# LowTemp_board_1.net
KiCad netlist of a schematic drawn in EAGLE
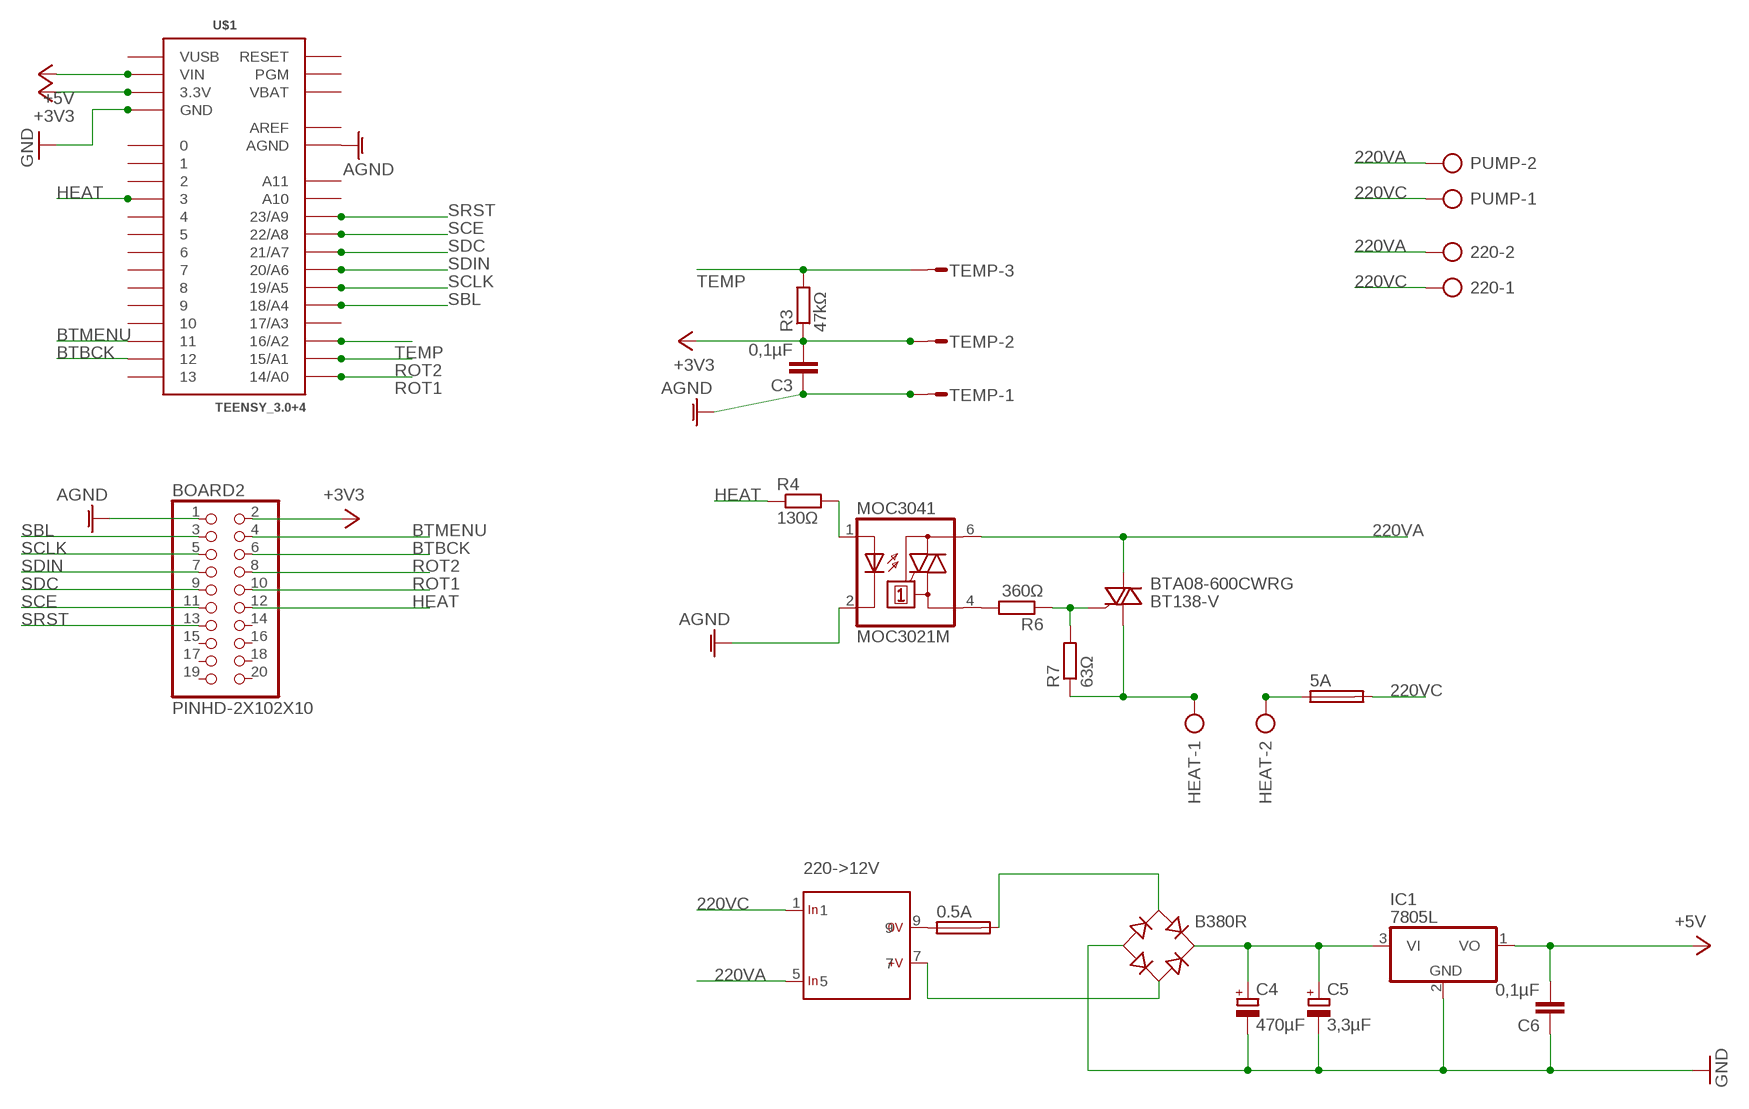
[diagram p0: schematic, sheet 1]

(export (version "E")
  (design (tool "Eeschema 10.0.6"))
  (components
    (comp (ref "0.5A")
      (value "SH22,5A")
      (footprint "eagle-import:SH22,5A")
      (fields (field (name "MPN") "0031.7701.11"))
      (libsource (lib "eagle-import") (part "SH22,5A"))
    )
    (comp (ref "5A")
      (value "SH22,5A")
      (footprint "eagle-import:SH22,5A")
      (fields (field (name "MPN") "0031.7701.11"))
      (libsource (lib "eagle-import") (part "SH22,5A"))
    )
    (comp (ref "220")
      (value "AK500/2-H")
      (footprint "eagle-import:AK500_2-H")
      (libsource (lib "eagle-import") (part "AK500/2-H"))
    )
    (comp (ref "220->12V")
      (value "SINGLE")
      (footprint "eagle-import:1")
      (libsource (lib "eagle-import") (part "SINGLE"))
    )
    (comp (ref "B380R")
      (value "RB1A")
      (footprint "eagle-import:RB1A")
      (libsource (lib "eagle-import") (part "RB1A"))
    )
    (comp (ref "BOARD2")
      (value "PINHD-2X102X10")
      (footprint "eagle-import:2X10")
      (libsource (lib "eagle-import") (part "PINHD-2X102X10"))
    )
    (comp (ref "BTA08-600CWRG")
      (value "BT138-V")
      (footprint "eagle-import:TO220BV")
      (libsource (lib "eagle-import") (part "BT138-V"))
    )
    (comp (ref "C3")
      (value "0,1µF")
      (footprint "eagle-import:C050-025X075")
      (libsource (lib "eagle-import") (part "C-EU050-025X075"))
    )
    (comp (ref "C4")
      (value "470µF")
      (footprint "eagle-import:E5-8,5")
      (libsource (lib "eagle-import") (part "CPOL-EUE5-8.5"))
    )
    (comp (ref "C5")
      (value "3,3µF")
      (footprint "eagle-import:TT2D4")
      (libsource (lib "eagle-import") (part "CPOL-EUTT2D4"))
    )
    (comp (ref "C6")
      (value "0,1µF")
      (footprint "eagle-import:C050-025X075")
      (libsource (lib "eagle-import") (part "C-EU050-025X075"))
    )
    (comp (ref "HEAT")
      (value "AK500/2-H")
      (footprint "eagle-import:AK500_2-H")
      (libsource (lib "eagle-import") (part "AK500/2-H"))
    )
    (comp (ref "IC1")
      (value "7805L")
      (footprint "eagle-import:TO92")
      (libsource (lib "eagle-import") (part "78L05"))
    )
    (comp (ref "MOC3041")
      (value "MOC3021M")
      (footprint "eagle-import:DIL06")
      (fields (field (name "MF") "FAIRCHILD SEMICONDUCTOR") (field (name "MPN") "MOC3021-M"))
      (libsource (lib "eagle-import") (part "MOC30M21"))
    )
    (comp (ref "PUMP")
      (value "AK500/2-H")
      (footprint "eagle-import:AK500_2-H")
      (libsource (lib "eagle-import") (part "AK500/2-H"))
    )
    (comp (ref "R3")
      (value "47kΩ")
      (footprint "eagle-import:0207_7")
      (libsource (lib "eagle-import") (part "R-EU_0207/7"))
    )
    (comp (ref "R4")
      (value "130Ω")
      (footprint "eagle-import:0207_7")
      (libsource (lib "eagle-import") (part "R-EU_0207/7"))
    )
    (comp (ref "R6")
      (value "360Ω")
      (footprint "eagle-import:0207_7")
      (libsource (lib "eagle-import") (part "R-EU_0207/7"))
    )
    (comp (ref "R7")
      (value "63Ω")
      (footprint "eagle-import:0207_7")
      (libsource (lib "eagle-import") (part "R-EU_0207/7"))
    )
    (comp (ref "TEMP")
      (value "S03P")
      (footprint "eagle-import:S03P")
      (libsource (lib "eagle-import") (part "S03P"))
    )
    (comp (ref "U$1")
      (value "TEENSY_3.0+4")
      (footprint "eagle-import:TEENSY_3.0+4")
      (libsource (lib "eagle-import") (part "TEENSY_3.0+4"))
    )
  )
  (nets
    (net (code "1") (name "+3V3") (class "Default")
      (node (ref "BOARD2") (pin "2") (pinfunction "2_2") (pintype "passive"))
      (node (ref "C3") (pin "2") (pinfunction "2_2") (pintype "passive"))
      (node (ref "R3") (pin "1") (pinfunction "1_1") (pintype "passive"))
      (node (ref "TEMP") (pin "2") (pinfunction "S_2") (pintype "passive"))
      (node (ref "U$1") (pin "3.3V") (pinfunction "3.3V_3.3V") (pintype "power_in"))
      (node (ref "U$1") (pin "3.3V1") (pinfunction "3.3V_3.3V1") (pintype "power_in"))
    )
    (net (code "2") (name "+5V") (class "Default")
      (node (ref "C6") (pin "2") (pinfunction "2_2") (pintype "passive"))
      (node (ref "IC1") (pin "1") (pinfunction "VO_1") (pintype "passive"))
      (node (ref "U$1") (pin "VIN") (pinfunction "VIN_VIN") (pintype "power_in"))
    )
    (net (code "3") (name "/220VA") (class "Default")
      (node (ref "220") (pin "2") (pinfunction "KL_2") (pintype "passive"))
      (node (ref "220->12V") (pin "5") (pinfunction "5_5") (pintype "input"))
      (node (ref "BTA08-600CWRG") (pin "T2") (pinfunction "A2_T2") (pintype "passive"))
      (node (ref "MOC3041") (pin "6") (pinfunction "A2_6") (pintype "passive"))
      (node (ref "PUMP") (pin "2") (pinfunction "KL_2") (pintype "passive"))
    )
    (net (code "4") (name "/220VC") (class "Default")
      (node (ref "220") (pin "1") (pinfunction "KL_1") (pintype "passive"))
      (node (ref "220->12V") (pin "1") (pinfunction "1_1") (pintype "input"))
      (node (ref "5A") (pin "2") (pinfunction "2_2") (pintype "passive"))
      (node (ref "PUMP") (pin "1") (pinfunction "KL_1") (pintype "passive"))
    )
    (net (code "5") (name "/AREF") (class "Default")
      (node (ref "U$1") (pin "AREF") (pinfunction "AREF_AREF") (pintype "power_in"))
    )
    (net (code "6") (name "/BTBCK") (class "Default")
      (node (ref "BOARD2") (pin "6") (pinfunction "6_6") (pintype "passive"))
      (node (ref "U$1") (pin "12") (pinfunction "12_12") (pintype "bidirectional"))
    )
    (net (code "7") (name "/BTMENU") (class "Default")
      (node (ref "BOARD2") (pin "4") (pinfunction "4_4") (pintype "passive"))
      (node (ref "U$1") (pin "11") (pinfunction "11_11") (pintype "bidirectional"))
    )
    (net (code "8") (name "/HEAT") (class "Default")
      (node (ref "BOARD2") (pin "12") (pinfunction "12_12") (pintype "passive"))
      (node (ref "R4") (pin "1") (pinfunction "1_1") (pintype "passive"))
      (node (ref "U$1") (pin "3") (pinfunction "3_3") (pintype "bidirectional"))
    )
    (net (code "9") (name "/ROT1") (class "Default")
      (node (ref "BOARD2") (pin "10") (pinfunction "10_10") (pintype "passive"))
      (node (ref "U$1") (pin "14/A0") (pinfunction "14/A0_14/A0") (pintype "bidirectional"))
    )
    (net (code "10") (name "/ROT2") (class "Default")
      (node (ref "BOARD2") (pin "8") (pinfunction "8_8") (pintype "passive"))
      (node (ref "U$1") (pin "15/A1") (pinfunction "15/A1_15/A1") (pintype "bidirectional"))
    )
    (net (code "11") (name "/SBL") (class "Default")
      (node (ref "BOARD2") (pin "3") (pinfunction "3_3") (pintype "passive"))
      (node (ref "U$1") (pin "18/A4") (pinfunction "18/A4_18/A4") (pintype "bidirectional"))
    )
    (net (code "12") (name "/SCE") (class "Default")
      (node (ref "BOARD2") (pin "11") (pinfunction "11_11") (pintype "passive"))
      (node (ref "U$1") (pin "22/A8") (pinfunction "22/A8_22/A8") (pintype "bidirectional"))
    )
    (net (code "13") (name "/SCLK") (class "Default")
      (node (ref "BOARD2") (pin "5") (pinfunction "5_5") (pintype "passive"))
      (node (ref "U$1") (pin "19/A5") (pinfunction "19/A5_19/A5") (pintype "bidirectional"))
    )
    (net (code "14") (name "/SDC") (class "Default")
      (node (ref "BOARD2") (pin "9") (pinfunction "9_9") (pintype "passive"))
      (node (ref "U$1") (pin "21/A7") (pinfunction "21/A7_21/A7") (pintype "bidirectional"))
    )
    (net (code "15") (name "/SDIN") (class "Default")
      (node (ref "BOARD2") (pin "7") (pinfunction "7_7") (pintype "passive"))
      (node (ref "U$1") (pin "20/A6") (pinfunction "20/A6_20/A6") (pintype "bidirectional"))
    )
    (net (code "16") (name "/SRST") (class "Default")
      (node (ref "BOARD2") (pin "13") (pinfunction "13_13") (pintype "passive"))
      (node (ref "U$1") (pin "23/A9") (pinfunction "23/A9_23/A9") (pintype "bidirectional"))
    )
    (net (code "17") (name "/TEMP") (class "Default")
      (node (ref "R3") (pin "2") (pinfunction "2_2") (pintype "passive"))
      (node (ref "TEMP") (pin "3") (pinfunction "S_3") (pintype "passive"))
      (node (ref "U$1") (pin "16/A2") (pinfunction "16/A2_16/A2") (pintype "bidirectional"))
    )
    (net (code "18") (name "/VBAT") (class "Default")
      (node (ref "U$1") (pin "VBAT") (pinfunction "VBAT_VBAT") (pintype "power_in"))
    )
    (net (code "19") (name "/VUSB") (class "Default")
      (node (ref "U$1") (pin "VUSB") (pinfunction "VUSB_VUSB") (pintype "power_in"))
    )
    (net (code "20") (name "AGND") (class "Default")
      (node (ref "BOARD2") (pin "1") (pinfunction "1_1") (pintype "passive"))
      (node (ref "C3") (pin "1") (pinfunction "1_1") (pintype "passive"))
      (node (ref "MOC3041") (pin "2") (pinfunction "C_2") (pintype "passive"))
      (node (ref "TEMP") (pin "1") (pinfunction "S_1") (pintype "passive"))
      (node (ref "U$1") (pin "AGND") (pinfunction "AGND_AGND") (pintype "power_in"))
    )
    (net (code "21") (name "GND") (class "Default")
      (node (ref "B380R") (pin "-") (pinfunction "-_-") (pintype "passive"))
      (node (ref "C4") (pin "-") (pinfunction "-_-") (pintype "passive"))
      (node (ref "C5") (pin "-") (pinfunction "-_-") (pintype "passive"))
      (node (ref "C6") (pin "1") (pinfunction "1_1") (pintype "passive"))
      (node (ref "IC1") (pin "2") (pinfunction "GND_2") (pintype "passive"))
      (node (ref "U$1") (pin "GND") (pinfunction "GND_GND") (pintype "power_in"))
      (node (ref "U$1") (pin "GND1") (pinfunction "GND_GND1") (pintype "power_in"))
    )
    (net (code "22") (name "Net-(0.5A-Pad1)") (class "Default")
      (node (ref "0.5A") (pin "1") (pinfunction "1_1") (pintype "passive"))
      (node (ref "220->12V") (pin "9") (pinfunction "9_9") (pintype "output"))
    )
    (net (code "23") (name "Net-(0.5A-Pad2)") (class "Default")
      (node (ref "0.5A") (pin "2") (pinfunction "2_2") (pintype "passive"))
      (node (ref "B380R") (pin "AC1") (pinfunction "AC1_AC1") (pintype "passive"))
    )
    (net (code "24") (name "Net-(220->12V-Pad7)") (class "Default")
      (node (ref "220->12V") (pin "7") (pinfunction "7_7") (pintype "output"))
      (node (ref "B380R") (pin "AC2") (pinfunction "AC2_AC2") (pintype "passive"))
    )
    (net (code "25") (name "Net-(BTA08-600CWRG-A1)") (class "Default")
      (node (ref "BTA08-600CWRG") (pin "T1") (pinfunction "A1_T1") (pintype "passive"))
      (node (ref "HEAT") (pin "1") (pinfunction "KL_1") (pintype "passive"))
      (node (ref "R7") (pin "1") (pinfunction "1_1") (pintype "passive"))
    )
    (net (code "26") (name "Net-(BTA08-600CWRG-PadG)") (class "Default")
      (node (ref "BTA08-600CWRG") (pin "G") (pinfunction "G_G") (pintype "passive"))
      (node (ref "R6") (pin "1") (pinfunction "1_1") (pintype "passive"))
      (node (ref "R7") (pin "2") (pinfunction "2_2") (pintype "passive"))
    )
    (net (code "27") (name "Net-(HEATB-KL)") (class "Default")
      (node (ref "5A") (pin "1") (pinfunction "1_1") (pintype "passive"))
      (node (ref "HEAT") (pin "2") (pinfunction "KL_2") (pintype "passive"))
    )
    (net (code "28") (name "Net-(IC1-VI)") (class "Default")
      (node (ref "B380R") (pin "+") (pinfunction "+_+") (pintype "passive"))
      (node (ref "C4") (pin "+") (pinfunction "+_+") (pintype "passive"))
      (node (ref "C5") (pin "+") (pinfunction "+_+") (pintype "passive"))
      (node (ref "IC1") (pin "3") (pinfunction "VI_3") (pintype "input"))
    )
    (net (code "29") (name "Net-(MOC3041-A)") (class "Default")
      (node (ref "MOC3041") (pin "1") (pinfunction "A_1") (pintype "passive"))
      (node (ref "R4") (pin "2") (pinfunction "2_2") (pintype "passive"))
    )
    (net (code "30") (name "Net-(MOC3041-A1)") (class "Default")
      (node (ref "MOC3041") (pin "4") (pinfunction "A1_4") (pintype "passive"))
      (node (ref "R6") (pin "2") (pinfunction "2_2") (pintype "passive"))
    )
    (net (code "31") (name "unconnected-(BOARD2-Pad14)") (class "Default")
      (node (ref "BOARD2") (pin "14") (pinfunction "14_14") (pintype "passive"))
    )
    (net (code "32") (name "unconnected-(BOARD2-Pad15)") (class "Default")
      (node (ref "BOARD2") (pin "15") (pinfunction "15_15") (pintype "passive"))
    )
    (net (code "33") (name "unconnected-(BOARD2-Pad16)") (class "Default")
      (node (ref "BOARD2") (pin "16") (pinfunction "16_16") (pintype "passive"))
    )
    (net (code "34") (name "unconnected-(BOARD2-Pad17)") (class "Default")
      (node (ref "BOARD2") (pin "17") (pinfunction "17_17") (pintype "passive"))
    )
    (net (code "35") (name "unconnected-(BOARD2-Pad18)") (class "Default")
      (node (ref "BOARD2") (pin "18") (pinfunction "18_18") (pintype "passive"))
    )
    (net (code "36") (name "unconnected-(BOARD2-Pad19)") (class "Default")
      (node (ref "BOARD2") (pin "19") (pinfunction "19_19") (pintype "passive"))
    )
    (net (code "37") (name "unconnected-(BOARD2-Pad20)") (class "Default")
      (node (ref "BOARD2") (pin "20") (pinfunction "20_20") (pintype "passive"))
    )
    (net (code "38") (name "unconnected-(U$1-Pad0)") (class "Default")
      (node (ref "U$1") (pin "0") (pinfunction "0_0") (pintype "bidirectional"))
    )
    (net (code "39") (name "unconnected-(U$1-Pad1)") (class "Default")
      (node (ref "U$1") (pin "1") (pinfunction "1_1") (pintype "bidirectional"))
    )
    (net (code "40") (name "unconnected-(U$1-Pad2)") (class "Default")
      (node (ref "U$1") (pin "2") (pinfunction "2_2") (pintype "bidirectional"))
    )
    (net (code "41") (name "unconnected-(U$1-Pad4)") (class "Default")
      (node (ref "U$1") (pin "4") (pinfunction "4_4") (pintype "bidirectional"))
    )
    (net (code "42") (name "unconnected-(U$1-Pad5)") (class "Default")
      (node (ref "U$1") (pin "5") (pinfunction "5_5") (pintype "bidirectional"))
    )
    (net (code "43") (name "unconnected-(U$1-Pad6)") (class "Default")
      (node (ref "U$1") (pin "6") (pinfunction "6_6") (pintype "bidirectional"))
    )
    (net (code "44") (name "unconnected-(U$1-Pad7)") (class "Default")
      (node (ref "U$1") (pin "7") (pinfunction "7_7") (pintype "bidirectional"))
    )
    (net (code "45") (name "unconnected-(U$1-Pad8)") (class "Default")
      (node (ref "U$1") (pin "8") (pinfunction "8_8") (pintype "bidirectional"))
    )
    (net (code "46") (name "unconnected-(U$1-Pad9)") (class "Default")
      (node (ref "U$1") (pin "9") (pinfunction "9_9") (pintype "bidirectional"))
    )
    (net (code "47") (name "unconnected-(U$1-Pad10)") (class "Default")
      (node (ref "U$1") (pin "10") (pinfunction "10_10") (pintype "bidirectional"))
    )
    (net (code "48") (name "unconnected-(U$1-Pad13)") (class "Default")
      (node (ref "U$1") (pin "13") (pinfunction "13_13") (pintype "bidirectional"))
    )
    (net (code "49") (name "unconnected-(U$1-Pad17{slash}A3)") (class "Default")
      (node (ref "U$1") (pin "17/A3") (pinfunction "17/A3_17/A3") (pintype "bidirectional"))
    )
    (net (code "50") (name "unconnected-(U$1-PadA10)") (class "Default")
      (node (ref "U$1") (pin "A10") (pinfunction "A10_A10") (pintype "bidirectional"))
    )
    (net (code "51") (name "unconnected-(U$1-PadA11)") (class "Default")
      (node (ref "U$1") (pin "A11") (pinfunction "A11_A11") (pintype "bidirectional"))
    )
    (net (code "52") (name "unconnected-(U$1-PadPGM)") (class "Default")
      (node (ref "U$1") (pin "PGM") (pinfunction "PGM_PGM") (pintype "bidirectional"))
    )
    (net (code "53") (name "unconnected-(U$1-PadRESET)") (class "Default")
      (node (ref "U$1") (pin "RESET") (pinfunction "RESET_RESET") (pintype "bidirectional"))
    )
  )
)
